# SCH_ESP_toster_V3.net
KiCad netlist of a schematic drawn in EasyEDA
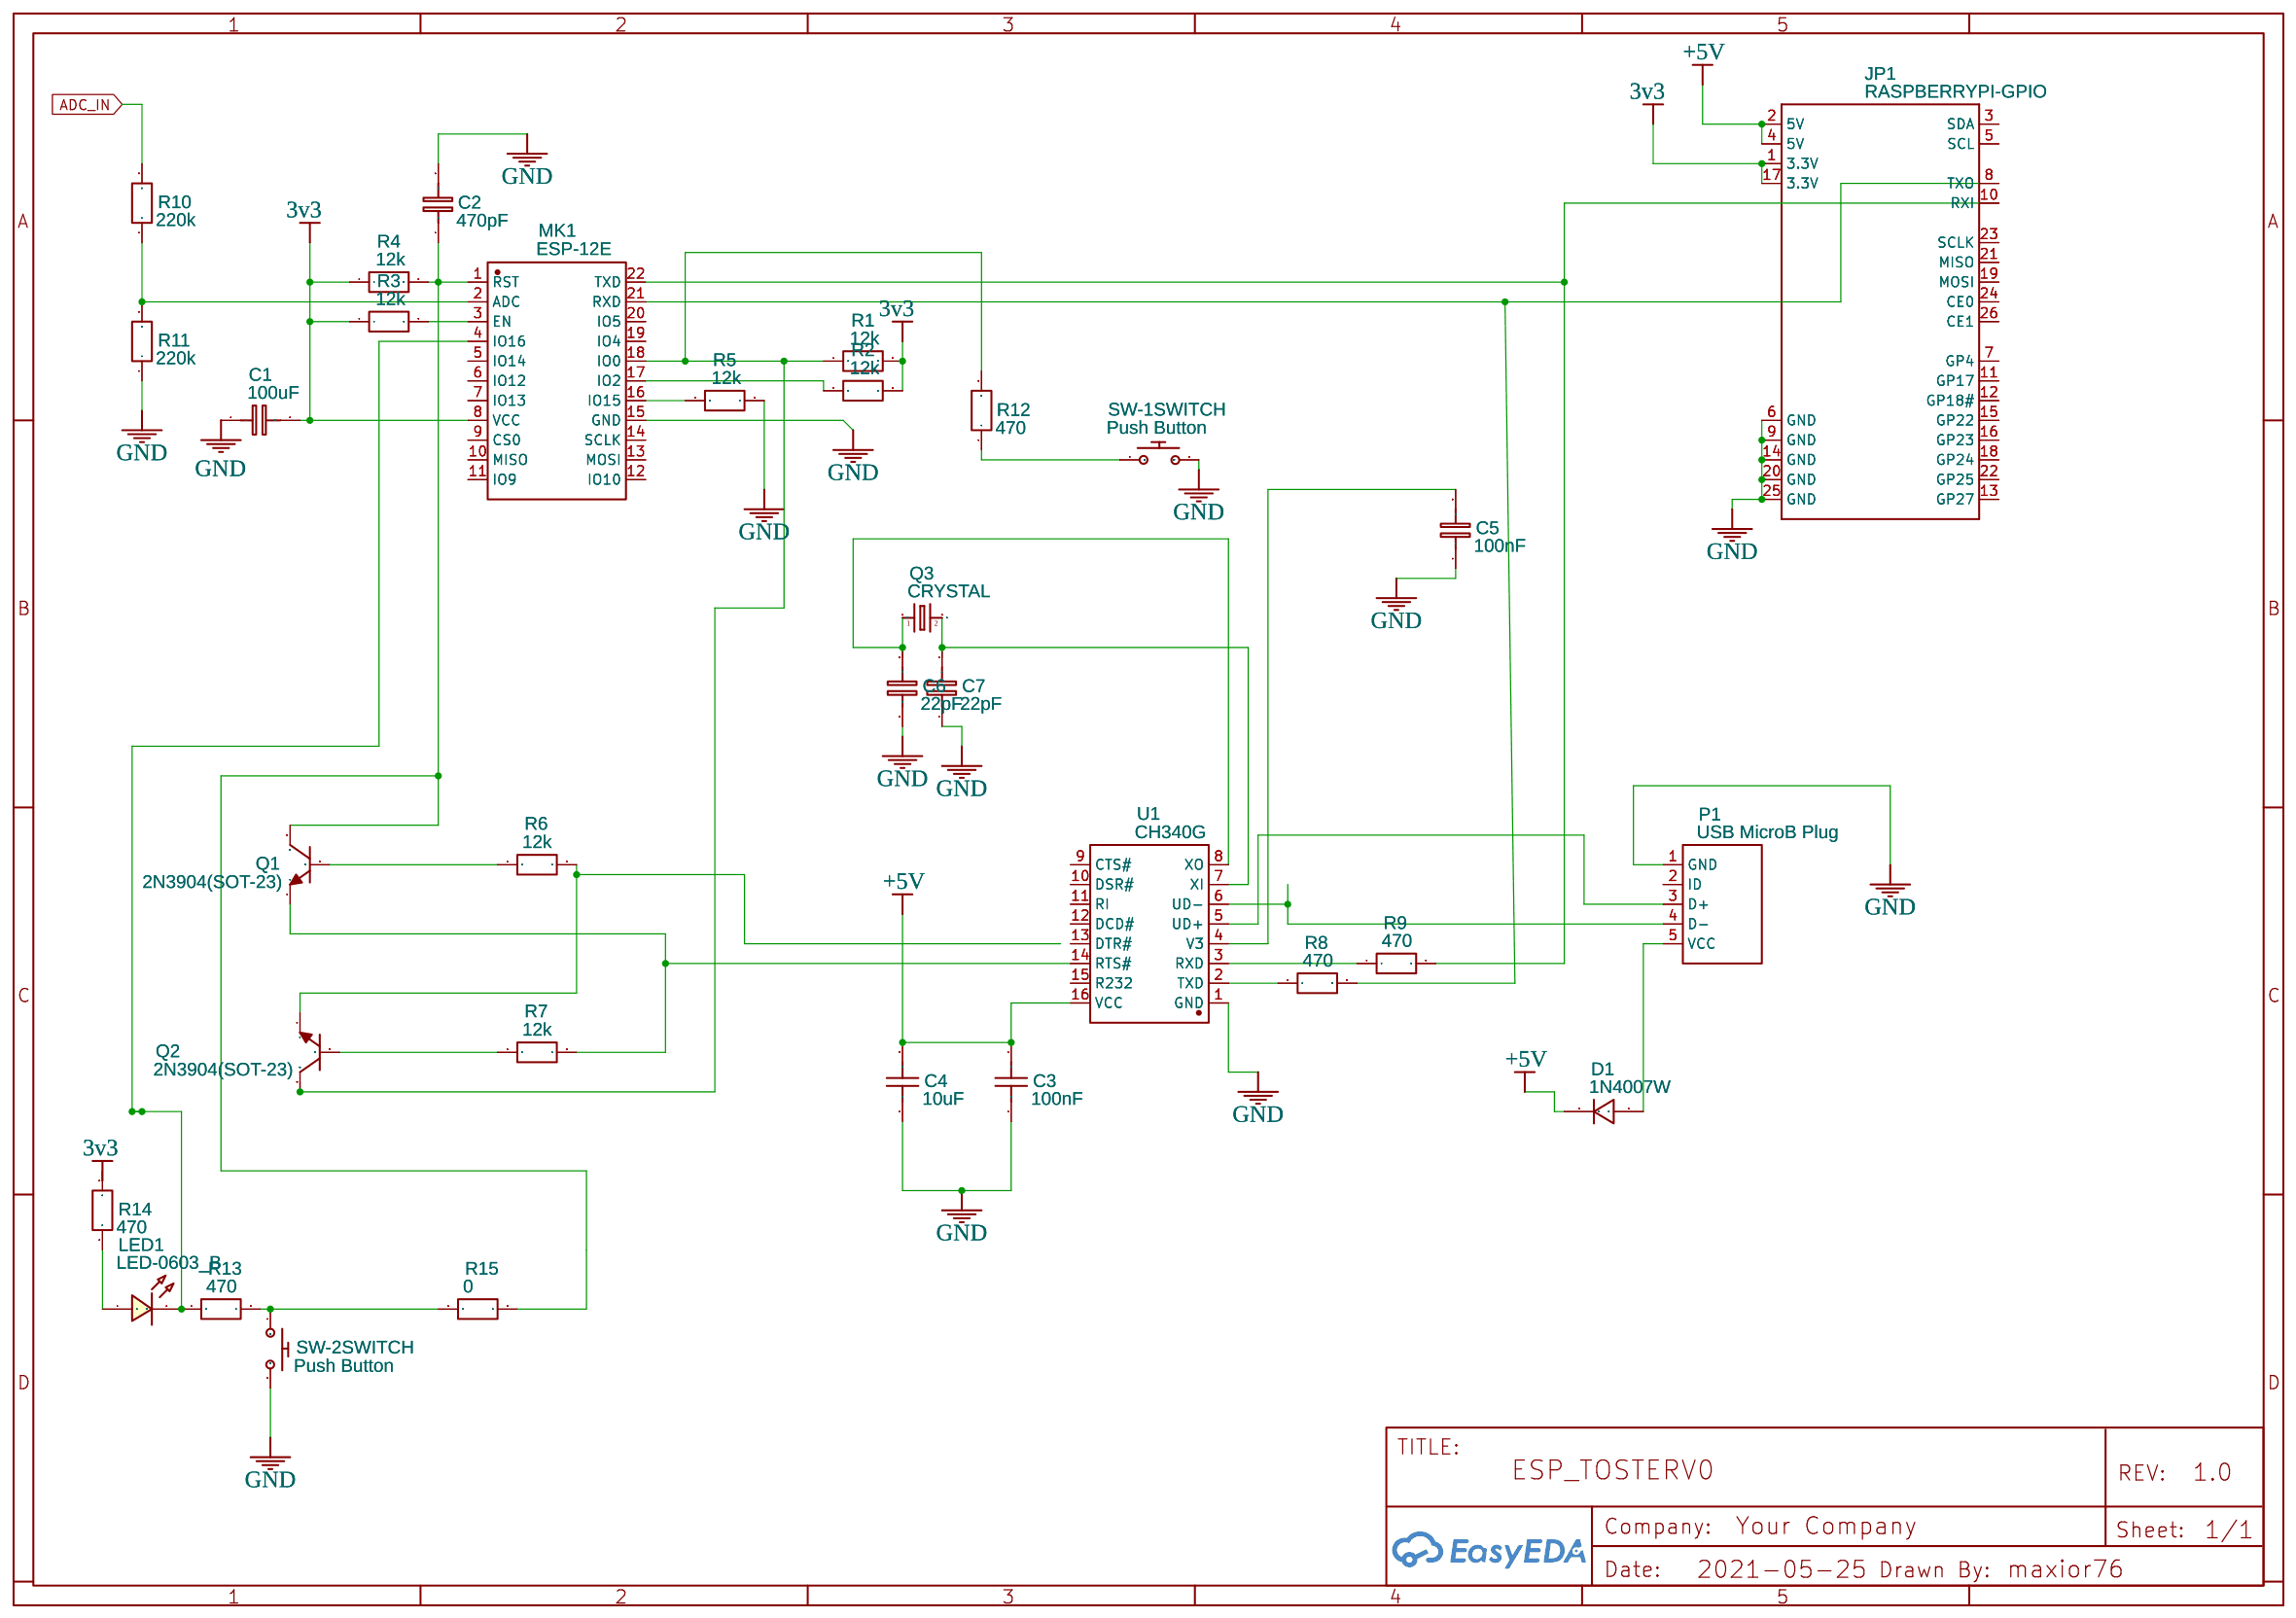
[diagram p0: schematic sheet]

(export (version "E")
  (design (tool "Eeschema 10.0.6"))
  (components
    (comp (ref "C1") (value "100uF") (libsource (lib "") (part "C_0603_EU_1")))
    (comp (ref "C2") (value "470pF") (libsource (lib "") (part "C_0603_EU_3")))
    (comp (ref "C3") (value "100nF") (libsource (lib "") (part "C_0603_US")))
    (comp (ref "C4") (value "10uF") (libsource (lib "") (part "C_0603_US")))
    (comp (ref "C5") (value "100nF") (libsource (lib "") (part "C_0603_EU_2")))
    (comp (ref "C6") (value "22pF") (libsource (lib "") (part "C_0603_EU")))
    (comp (ref "C7") (value "22pF") (libsource (lib "") (part "C_0603_EU")))
    (comp (ref "D1")
      (value "1N4007W")
      (fields (field (name "BOM_Supplier Part") "C328592"))
      (libsource (lib "") (part "1N4007W"))
    )
    (comp (ref "JP1") (value "RASPBERRYPI-GPIO") (libsource (lib "") (part "RASPBERRYPI-GPIO")))
    (comp (ref "LED1")
      (value "LED-0603_B")
      (fields
        (field (name "BOM_Manufacturer Part") "19-217/R6C-AL1M2VY/3T")
        (field (name "BOM_Supplier Part") "C72044")
      )
      (libsource (lib "") (part "LED-0603_R"))
    )
    (comp (ref "MK1")
      (value "ESP-12E")
      (fields (field (name "BOM_Supplier Part") "C89297"))
      (libsource (lib "") (part "ESP-12E"))
    )
    (comp (ref "P1") (value "USB MicroB Plug") (libsource (lib "") (part "USB MicroB Plug")))
    (comp (ref "Q1")
      (value "2N3904(SOT-23)")
      (fields
        (field (name "BOM_Manufacturer Part") "2n3904S-RTK/PS")
        (field (name "BOM_Supplier Part") "C18536")
      )
      (libsource (lib "") (part "2N3904(SOT-23)_1"))
    )
    (comp (ref "Q2")
      (value "2N3904(SOT-23)")
      (fields
        (field (name "BOM_Manufacturer Part") "2n3904S-RTK/PS")
        (field (name "BOM_Supplier Part") "C18536")
      )
      (libsource (lib "") (part "2N3904(SOT-23)"))
    )
    (comp (ref "Q3") (value "CRYSTAL") (libsource (lib "") (part "CRYSTAL")))
    (comp (ref "R1") (value "12k") (libsource (lib "") (part "R_0603_EU")))
    (comp (ref "R2") (value "12k") (libsource (lib "") (part "R_0603_EU")))
    (comp (ref "R3") (value "12k") (libsource (lib "") (part "R_0603_EU")))
    (comp (ref "R4") (value "12k") (libsource (lib "") (part "R_0603_EU")))
    (comp (ref "R5") (value "12k") (libsource (lib "") (part "R_0603_EU")))
    (comp (ref "R6") (value "12k") (libsource (lib "") (part "R_0603_EU")))
    (comp (ref "R7") (value "12k") (libsource (lib "") (part "R_0603_EU")))
    (comp (ref "R8") (value "470") (libsource (lib "") (part "R_0603_EU")))
    (comp (ref "R9") (value "470") (libsource (lib "") (part "R_0603_EU")))
    (comp (ref "R10") (value "220k") (libsource (lib "") (part "R_0603_EU_1")))
    (comp (ref "R11") (value "220k") (libsource (lib "") (part "R_0603_EU_1")))
    (comp (ref "R12") (value "470") (libsource (lib "") (part "R_0603_EU_1")))
    (comp (ref "R13") (value "470") (libsource (lib "") (part "R_0603_EU")))
    (comp (ref "R14") (value "470") (libsource (lib "") (part "R_0603_EU_1")))
    (comp (ref "R15") (value "0") (libsource (lib "") (part "R_0603_EU")))
    (comp (ref "SW-1SWITCH")
      (value "Push Button")
      (fields (field (name "BOM_Supplier Part") "COM-08720"))
      (libsource (lib "") (part "Push Button"))
    )
    (comp (ref "SW-2SWITCH")
      (value "Push Button")
      (fields (field (name "BOM_Supplier Part") "COM-08720"))
      (libsource (lib "") (part "Push Button_1"))
    )
    (comp (ref "U1")
      (value "CH340G")
      (fields (field (name "BOM_Supplier Part") "C14267"))
      (libsource (lib "") (part "CH340G"))
    )
  )
  (nets
    (net (code "1") (name "+5V") (class "Default")
      (node (ref "C3") (pin "2") (pinfunction "2_2") (pintype "unspecified"))
      (node (ref "C4") (pin "2") (pinfunction "2_2") (pintype "unspecified"))
      (node (ref "D1") (pin "1") (pinfunction "1_1") (pintype "unspecified"))
      (node (ref "JP1") (pin "2") (pinfunction "5V_2") (pintype "passive"))
      (node (ref "JP1") (pin "4") (pinfunction "5V_4") (pintype "passive"))
      (node (ref "U1") (pin "16") (pinfunction "VCC_16") (pintype "unspecified"))
    )
    (net (code "2") (name "3v3") (class "Default")
      (node (ref "C1") (pin "2") (pinfunction "2_2") (pintype "unspecified"))
      (node (ref "JP1") (pin "1") (pinfunction "3.3V_1") (pintype "passive"))
      (node (ref "JP1") (pin "17") (pinfunction "3.3V_17") (pintype "passive"))
      (node (ref "MK1") (pin "8") (pinfunction "VCC_8") (pintype "unspecified"))
      (node (ref "R1") (pin "2") (pinfunction "2_2") (pintype "unspecified"))
      (node (ref "R14") (pin "2") (pinfunction "2_2") (pintype "unspecified"))
      (node (ref "R2") (pin "2") (pinfunction "2_2") (pintype "unspecified"))
      (node (ref "R3") (pin "1") (pinfunction "1_1") (pintype "unspecified"))
      (node (ref "R4") (pin "1") (pinfunction "1_1") (pintype "unspecified"))
    )
    (net (code "3") (name "ADC_IN") (class "Default")
      (node (ref "R10") (pin "2") (pinfunction "2_2") (pintype "unspecified"))
    )
    (net (code "4") (name "GND") (class "Default")
      (node (ref "C1") (pin "1") (pinfunction "1_1") (pintype "unspecified"))
      (node (ref "C2") (pin "2") (pinfunction "2_2") (pintype "unspecified"))
      (node (ref "C3") (pin "1") (pinfunction "1_1") (pintype "unspecified"))
      (node (ref "C4") (pin "1") (pinfunction "1_1") (pintype "unspecified"))
      (node (ref "C5") (pin "1") (pinfunction "1_1") (pintype "unspecified"))
      (node (ref "C6") (pin "1") (pinfunction "1_1") (pintype "unspecified"))
      (node (ref "C7") (pin "1") (pinfunction "1_1") (pintype "unspecified"))
      (node (ref "JP1") (pin "14") (pinfunction "GND_14") (pintype "passive"))
      (node (ref "JP1") (pin "20") (pinfunction "GND_20") (pintype "passive"))
      (node (ref "JP1") (pin "25") (pinfunction "GND_25") (pintype "passive"))
      (node (ref "JP1") (pin "6") (pinfunction "GND_6") (pintype "passive"))
      (node (ref "JP1") (pin "9") (pinfunction "GND_9") (pintype "passive"))
      (node (ref "MK1") (pin "15") (pinfunction "GND_15") (pintype "unspecified"))
      (node (ref "P1") (pin "1") (pinfunction "GND_1") (pintype "unspecified"))
      (node (ref "R11") (pin "1") (pinfunction "1_1") (pintype "unspecified"))
      (node (ref "R5") (pin "2") (pinfunction "2_2") (pintype "unspecified"))
      (node (ref "SW-1SWITCH") (pin "2") (pinfunction "P$2_2") (pintype "unspecified"))
      (node (ref "SW-2SWITCH") (pin "2") (pinfunction "P$2_2") (pintype "unspecified"))
      (node (ref "U1") (pin "1") (pinfunction "GND_1") (pintype "unspecified"))
    )
    (net (code "5") (name "Net-(JP1-RXI)") (class "Default")
      (node (ref "JP1") (pin "10") (pinfunction "RXI_10") (pintype "input"))
      (node (ref "MK1") (pin "22") (pinfunction "TXD_22") (pintype "unspecified"))
      (node (ref "R9") (pin "2") (pinfunction "2_2") (pintype "unspecified"))
    )
    (net (code "6") (name "Net-(JP1-TXO)") (class "Default")
      (node (ref "JP1") (pin "8") (pinfunction "TXO_8") (pintype "output"))
      (node (ref "MK1") (pin "21") (pinfunction "RXD_21") (pintype "unspecified"))
      (node (ref "R8") (pin "2") (pinfunction "2_2") (pintype "unspecified"))
    )
    (net (code "7") (name "Net-(LED1-Pad1)") (class "Default")
      (node (ref "LED1") (pin "1") (pinfunction "1_1") (pintype "unspecified"))
      (node (ref "R14") (pin "1") (pinfunction "1_1") (pintype "unspecified"))
    )
    (net (code "8") (name "Net-(MK1-ADC)") (class "Default")
      (node (ref "MK1") (pin "2") (pinfunction "ADC_2") (pintype "unspecified"))
      (node (ref "R10") (pin "1") (pinfunction "1_1") (pintype "unspecified"))
      (node (ref "R11") (pin "2") (pinfunction "2_2") (pintype "unspecified"))
    )
    (net (code "9") (name "Net-(MK1-EN)") (class "Default")
      (node (ref "MK1") (pin "3") (pinfunction "EN_3") (pintype "unspecified"))
      (node (ref "R3") (pin "2") (pinfunction "2_2") (pintype "unspecified"))
    )
    (net (code "10") (name "Net-(MK1-IO0)") (class "Default")
      (node (ref "MK1") (pin "18") (pinfunction "IO0_18") (pintype "unspecified"))
      (node (ref "Q2") (pin "3") (pinfunction "C_3") (pintype "input"))
      (node (ref "R1") (pin "1") (pinfunction "1_1") (pintype "unspecified"))
      (node (ref "R12") (pin "2") (pinfunction "2_2") (pintype "unspecified"))
    )
    (net (code "11") (name "Net-(MK1-IO2)") (class "Default")
      (node (ref "MK1") (pin "17") (pinfunction "IO2_17") (pintype "unspecified"))
      (node (ref "R2") (pin "1") (pinfunction "1_1") (pintype "unspecified"))
    )
    (net (code "12") (name "Net-(MK1-IO15)") (class "Default")
      (node (ref "MK1") (pin "16") (pinfunction "IO15_16") (pintype "unspecified"))
      (node (ref "R5") (pin "1") (pinfunction "1_1") (pintype "unspecified"))
    )
    (net (code "13") (name "Net-(MK1-IO16)") (class "Default")
      (node (ref "LED1") (pin "2") (pinfunction "2_2") (pintype "unspecified"))
      (node (ref "MK1") (pin "4") (pinfunction "IO16_4") (pintype "unspecified"))
      (node (ref "R13") (pin "1") (pinfunction "1_1") (pintype "unspecified"))
    )
    (net (code "14") (name "Net-(MK1-RST)") (class "Default")
      (node (ref "C2") (pin "1") (pinfunction "1_1") (pintype "unspecified"))
      (node (ref "MK1") (pin "1") (pinfunction "RST_1") (pintype "unspecified"))
      (node (ref "Q1") (pin "3") (pinfunction "C_3") (pintype "input"))
      (node (ref "R15") (pin "2") (pinfunction "2_2") (pintype "unspecified"))
      (node (ref "R4") (pin "2") (pinfunction "2_2") (pintype "unspecified"))
    )
    (net (code "15") (name "Net-(P1-D+)") (class "Default")
      (node (ref "P1") (pin "3") (pinfunction "D+_3") (pintype "unspecified"))
      (node (ref "U1") (pin "5") (pinfunction "UD+_5") (pintype "unspecified"))
    )
    (net (code "16") (name "Net-(P1-D-)") (class "Default")
      (node (ref "P1") (pin "4") (pinfunction "D-_4") (pintype "unspecified"))
      (node (ref "U1") (pin "6") (pinfunction "UD-_6") (pintype "unspecified"))
    )
    (net (code "17") (name "Net-(P1-VCC)") (class "Default")
      (node (ref "D1") (pin "2") (pinfunction "2_2") (pintype "unspecified"))
      (node (ref "P1") (pin "5") (pinfunction "VCC_5") (pintype "unspecified"))
    )
    (net (code "18") (name "Net-(Q1-B)") (class "Default")
      (node (ref "Q1") (pin "2") (pinfunction "B_2") (pintype "input"))
      (node (ref "R6") (pin "1") (pinfunction "1_1") (pintype "unspecified"))
    )
    (net (code "19") (name "Net-(Q1-E)") (class "Default")
      (node (ref "Q1") (pin "1") (pinfunction "E_1") (pintype "input"))
      (node (ref "R7") (pin "2") (pinfunction "2_2") (pintype "unspecified"))
      (node (ref "U1") (pin "14") (pinfunction "RTS#_14") (pintype "unspecified"))
    )
    (net (code "20") (name "Net-(Q2-B)") (class "Default")
      (node (ref "Q2") (pin "2") (pinfunction "B_2") (pintype "input"))
      (node (ref "R7") (pin "1") (pinfunction "1_1") (pintype "unspecified"))
    )
    (net (code "21") (name "Net-(Q2-E)") (class "Default")
      (node (ref "Q2") (pin "1") (pinfunction "E_1") (pintype "input"))
      (node (ref "R6") (pin "2") (pinfunction "2_2") (pintype "unspecified"))
    )
    (net (code "22") (name "Net-(SW-1SWITCH-P$1)") (class "Default")
      (node (ref "R12") (pin "1") (pinfunction "1_1") (pintype "unspecified"))
      (node (ref "SW-1SWITCH") (pin "1") (pinfunction "P$1_1") (pintype "unspecified"))
    )
    (net (code "23") (name "Net-(SW-2SWITCH-P$1)") (class "Default")
      (node (ref "R13") (pin "2") (pinfunction "2_2") (pintype "unspecified"))
      (node (ref "R15") (pin "1") (pinfunction "1_1") (pintype "unspecified"))
      (node (ref "SW-2SWITCH") (pin "1") (pinfunction "P$1_1") (pintype "unspecified"))
    )
    (net (code "24") (name "Net-(U1-RXD)") (class "Default")
      (node (ref "R9") (pin "1") (pinfunction "1_1") (pintype "unspecified"))
      (node (ref "U1") (pin "3") (pinfunction "RXD_3") (pintype "unspecified"))
    )
    (net (code "25") (name "Net-(U1-TXD)") (class "Default")
      (node (ref "R8") (pin "1") (pinfunction "1_1") (pintype "unspecified"))
      (node (ref "U1") (pin "2") (pinfunction "TXD_2") (pintype "unspecified"))
    )
    (net (code "26") (name "Net-(U1-V3)") (class "Default")
      (node (ref "C5") (pin "2") (pinfunction "2_2") (pintype "unspecified"))
      (node (ref "U1") (pin "4") (pinfunction "V3_4") (pintype "unspecified"))
    )
    (net (code "27") (name "Net-(U1-XI)") (class "Default")
      (node (ref "C7") (pin "2") (pinfunction "2_2") (pintype "unspecified"))
      (node (ref "Q3") (pin "2") (pinfunction "2_2") (pintype "unspecified"))
      (node (ref "U1") (pin "7") (pinfunction "XI_7") (pintype "unspecified"))
    )
    (net (code "28") (name "Net-(U1-XO)") (class "Default")
      (node (ref "C6") (pin "2") (pinfunction "2_2") (pintype "unspecified"))
      (node (ref "Q3") (pin "1") (pinfunction "1_1") (pintype "unspecified"))
      (node (ref "U1") (pin "8") (pinfunction "XO_8") (pintype "unspecified"))
    )
    (net (code "29") (name "unconnected-(JP1-CE0-Pad24)") (class "Default")
      (node (ref "JP1") (pin "24") (pinfunction "CE0_24") (pintype "output"))
    )
    (net (code "30") (name "unconnected-(JP1-CE1-Pad26)") (class "Default")
      (node (ref "JP1") (pin "26") (pinfunction "CE1_26") (pintype "output"))
    )
    (net (code "31") (name "unconnected-(JP1-GP4-Pad7)") (class "Default")
      (node (ref "JP1") (pin "7") (pinfunction "GP4_7") (pintype "unspecified"))
    )
    (net (code "32") (name "unconnected-(JP1-GP17-Pad11)") (class "Default")
      (node (ref "JP1") (pin "11") (pinfunction "GP17_11") (pintype "unspecified"))
    )
    (net (code "33") (name "unconnected-(JP1-GP18#-Pad12)") (class "Default")
      (node (ref "JP1") (pin "12") (pinfunction "GP18#_12") (pintype "unspecified"))
    )
    (net (code "34") (name "unconnected-(JP1-GP22-Pad15)") (class "Default")
      (node (ref "JP1") (pin "15") (pinfunction "GP22_15") (pintype "unspecified"))
    )
    (net (code "35") (name "unconnected-(JP1-GP23-Pad16)") (class "Default")
      (node (ref "JP1") (pin "16") (pinfunction "GP23_16") (pintype "unspecified"))
    )
    (net (code "36") (name "unconnected-(JP1-GP24-Pad18)") (class "Default")
      (node (ref "JP1") (pin "18") (pinfunction "GP24_18") (pintype "unspecified"))
    )
    (net (code "37") (name "unconnected-(JP1-GP25-Pad22)") (class "Default")
      (node (ref "JP1") (pin "22") (pinfunction "GP25_22") (pintype "unspecified"))
    )
    (net (code "38") (name "unconnected-(JP1-GP27-Pad13)") (class "Default")
      (node (ref "JP1") (pin "13") (pinfunction "GP27_13") (pintype "unspecified"))
    )
    (net (code "39") (name "unconnected-(JP1-MISO-Pad21)") (class "Default")
      (node (ref "JP1") (pin "21") (pinfunction "MISO_21") (pintype "input"))
    )
    (net (code "40") (name "unconnected-(JP1-MOSI-Pad19)") (class "Default")
      (node (ref "JP1") (pin "19") (pinfunction "MOSI_19") (pintype "output"))
    )
    (net (code "41") (name "unconnected-(JP1-SCL-Pad5)") (class "Default")
      (node (ref "JP1") (pin "5") (pinfunction "SCL_5") (pintype "unspecified"))
    )
    (net (code "42") (name "unconnected-(JP1-SCLK-Pad23)") (class "Default")
      (node (ref "JP1") (pin "23") (pinfunction "SCLK_23") (pintype "output"))
    )
    (net (code "43") (name "unconnected-(JP1-SDA-Pad3)") (class "Default")
      (node (ref "JP1") (pin "3") (pinfunction "SDA_3") (pintype "unspecified"))
    )
    (net (code "44") (name "unconnected-(MK1-CS0-Pad9)") (class "Default")
      (node (ref "MK1") (pin "9") (pinfunction "CS0_9") (pintype "unspecified"))
    )
    (net (code "45") (name "unconnected-(MK1-IO4-Pad19)") (class "Default")
      (node (ref "MK1") (pin "19") (pinfunction "IO4_19") (pintype "unspecified"))
    )
    (net (code "46") (name "unconnected-(MK1-IO5-Pad20)") (class "Default")
      (node (ref "MK1") (pin "20") (pinfunction "IO5_20") (pintype "unspecified"))
    )
    (net (code "47") (name "unconnected-(MK1-IO9-Pad11)") (class "Default")
      (node (ref "MK1") (pin "11") (pinfunction "IO9_11") (pintype "unspecified"))
    )
    (net (code "48") (name "unconnected-(MK1-IO10-Pad12)") (class "Default")
      (node (ref "MK1") (pin "12") (pinfunction "IO10_12") (pintype "unspecified"))
    )
    (net (code "49") (name "unconnected-(MK1-IO12-Pad6)") (class "Default")
      (node (ref "MK1") (pin "6") (pinfunction "IO12_6") (pintype "unspecified"))
    )
    (net (code "50") (name "unconnected-(MK1-IO13-Pad7)") (class "Default")
      (node (ref "MK1") (pin "7") (pinfunction "IO13_7") (pintype "unspecified"))
    )
    (net (code "51") (name "unconnected-(MK1-IO14-Pad5)") (class "Default")
      (node (ref "MK1") (pin "5") (pinfunction "IO14_5") (pintype "unspecified"))
    )
    (net (code "52") (name "unconnected-(MK1-MISO-Pad10)") (class "Default")
      (node (ref "MK1") (pin "10") (pinfunction "MISO_10") (pintype "unspecified"))
    )
    (net (code "53") (name "unconnected-(MK1-MOSI-Pad13)") (class "Default")
      (node (ref "MK1") (pin "13") (pinfunction "MOSI_13") (pintype "unspecified"))
    )
    (net (code "54") (name "unconnected-(MK1-SCLK-Pad14)") (class "Default")
      (node (ref "MK1") (pin "14") (pinfunction "SCLK_14") (pintype "unspecified"))
    )
    (net (code "55") (name "unconnected-(P1-ID-Pad2)") (class "Default")
      (node (ref "P1") (pin "2") (pinfunction "ID_2") (pintype "unspecified"))
    )
    (net (code "56") (name "unconnected-(U1-CTS#-Pad9)") (class "Default")
      (node (ref "U1") (pin "9") (pinfunction "CTS#_9") (pintype "unspecified"))
    )
    (net (code "57") (name "unconnected-(U1-DCD#-Pad12)") (class "Default")
      (node (ref "U1") (pin "12") (pinfunction "DCD#_12") (pintype "unspecified"))
    )
    (net (code "58") (name "unconnected-(U1-DSR#-Pad10)") (class "Default")
      (node (ref "U1") (pin "10") (pinfunction "DSR#_10") (pintype "unspecified"))
    )
    (net (code "59") (name "unconnected-(U1-DTR#-Pad13)") (class "Default")
      (node (ref "U1") (pin "13") (pinfunction "DTR#_13") (pintype "unspecified"))
    )
    (net (code "60") (name "unconnected-(U1-R232-Pad15)") (class "Default")
      (node (ref "U1") (pin "15") (pinfunction "R232_15") (pintype "unspecified"))
    )
    (net (code "61") (name "unconnected-(U1-RI-Pad11)") (class "Default")
      (node (ref "U1") (pin "11") (pinfunction "RI_11") (pintype "unspecified"))
    )
  )
)
